# NanoEEG_v1_ADC.net
KiCad netlist of a schematic drawn in Altium Designer
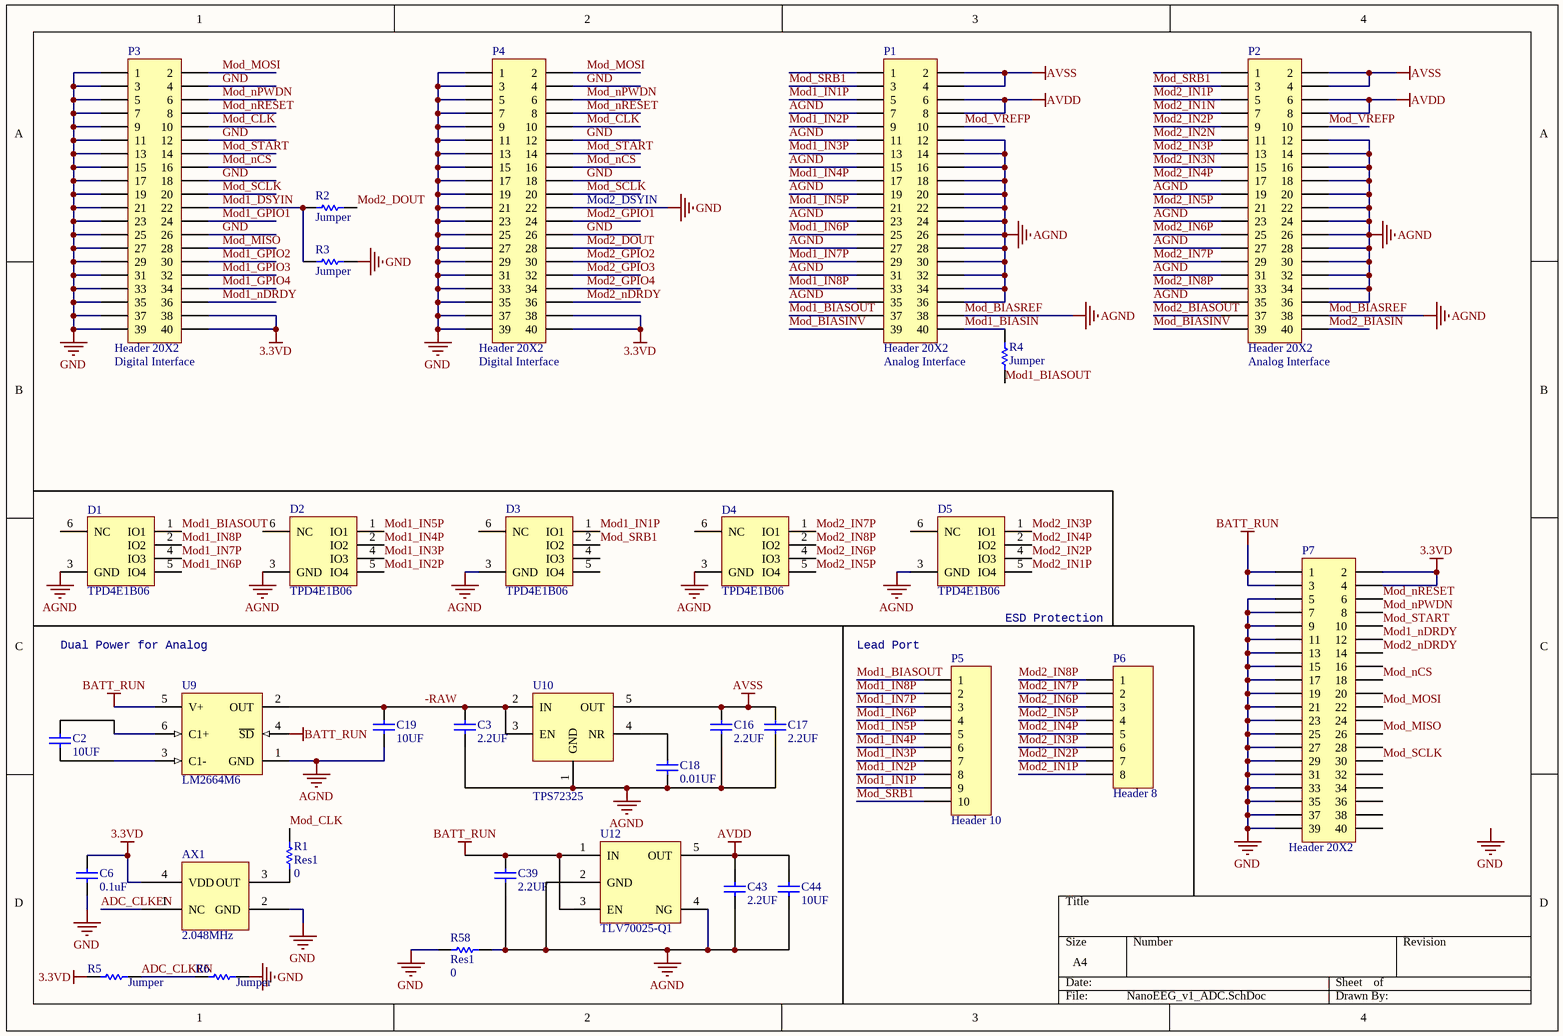
[diagram p0: NanoEEG_v1_ADC.SchDoc]

(export (version "E")
  (design (tool "Eeschema 10.0.6"))
  (components
    (comp (ref "AX1")
      (value "2.048MHz")
      (footprint "EPSON-SG-310-4_V")
      (libsource (lib "SMARTCAR09") (part "Active Cyrstal 5x7"))
    )
    (comp (ref "C2") (value "10UF") (footprint "RESC2012N") (libsource (lib "智能车") (part "CAP_0603")))
    (comp (ref "C3") (value "2.2UF") (footprint "RESC2012N") (libsource (lib "智能车") (part "CAP_0402")))
    (comp (ref "C6") (value "0.1uF") (footprint "RESC1608N") (libsource (lib "智能车") (part "电容")))
    (comp (ref "C16") (value "2.2UF") (footprint "RESC1608N") (libsource (lib "智能车") (part "RESC2012N")))
    (comp (ref "C17") (value "2.2UF") (footprint "RESC1608N") (libsource (lib "智能车") (part "RESC2012N")))
    (comp (ref "C18") (value "0.01UF") (footprint "RESC1608N") (libsource (lib "智能车") (part "RESC1608N")))
    (comp (ref "C19") (value "10UF") (footprint "RESC2012N") (libsource (lib "智能车") (part "CAP_0603")))
    (comp (ref "C39") (value "2.2UF") (footprint "RESC2012N") (libsource (lib "智能车") (part "CAP_0402")))
    (comp (ref "C43") (value "2.2UF") (footprint "RESC2012N") (libsource (lib "智能车") (part "CAP_0402")))
    (comp (ref "C44") (value "10UF") (footprint "RESC2012N") (libsource (lib "智能车") (part "CAP_0603")))
    (comp (ref "D1")
      (value "TPD4E1B06")
      (footprint "erjiguan")
      (libsource (lib "Trans_ETH") (part "TPD4E1B06"))
    )
    (comp (ref "D2")
      (value "TPD4E1B06")
      (footprint "erjiguan")
      (libsource (lib "Trans_ETH") (part "TPD4E1B06"))
    )
    (comp (ref "D3")
      (value "TPD4E1B06")
      (footprint "erjiguan")
      (libsource (lib "Trans_ETH") (part "TPD4E1B06"))
    )
    (comp (ref "D4")
      (value "TPD4E1B06")
      (footprint "erjiguan")
      (libsource (lib "Trans_ETH") (part "TPD4E1B06"))
    )
    (comp (ref "D5")
      (value "TPD4E1B06")
      (footprint "erjiguan")
      (libsource (lib "Trans_ETH") (part "TPD4E1B06"))
    )
    (comp (ref "P1")
      (value "Header 20X2")
      (footprint "FCI-B2B-0.8mm-40p-male")
      (description "Header, 20-Pin, Dual row")
      (fields (field (name "PUBLISHER") "Altium Limited"))
      (libsource (lib "Miscellaneous Connectors") (part "Header 20X2"))
    )
    (comp (ref "P2")
      (value "Header 20X2")
      (footprint "FCI-B2B-0.8mm-40p-MALE")
      (description "Header, 20-Pin, Dual row")
      (fields (field (name "PUBLISHER") "Altium Limited"))
      (libsource (lib "Miscellaneous Connectors") (part "Header 20X2"))
    )
    (comp (ref "P3")
      (value "Header 20X2")
      (footprint "FCI-B2B-0.8mm-40p-male")
      (description "Header, 20-Pin, Dual row")
      (fields (field (name "PUBLISHER") "Altium Limited"))
      (libsource (lib "Miscellaneous Connectors") (part "Header 20X2"))
    )
    (comp (ref "P4")
      (value "Header 20X2")
      (footprint "FCI-B2B-0.8mm-40p-MALE")
      (description "Header, 20-Pin, Dual row")
      (fields (field (name "PUBLISHER") "Altium Limited"))
      (libsource (lib "Miscellaneous Connectors") (part "Header 20X2"))
    )
    (comp (ref "P5")
      (value "Header 10")
      (footprint "PH2.0-WS-10P")
      (description "Header, 10-Pin")
      (fields (field (name "PUBLISHER") "Altium Limited"))
      (libsource (lib "Miscellaneous Connectors") (part "Header 10"))
    )
    (comp (ref "P6")
      (value "Header 8")
      (footprint "PH2.0-WS-8P")
      (description "Header, 8-Pin")
      (fields (field (name "PUBLISHER") "Altium Limited"))
      (libsource (lib "Miscellaneous Connectors") (part "Header 8"))
    )
    (comp (ref "P7")
      (value "Header 20X2")
      (footprint "FCI-B2B-0.8mm-40p-MALE")
      (description "Header, 20-Pin, Dual row")
      (fields (field (name "PUBLISHER") "Altium Limited"))
      (libsource (lib "Miscellaneous Connectors") (part "Header 20X2"))
    )
    (comp (ref "R1")
      (value "Res1")
      (footprint "RESC1608N")
      (description "Resistor")
      (fields (field (name "ALTIUM_VALUE") "0") (field (name "PUBLISHER") "Altium Limited"))
      (libsource (lib "Miscellaneous Devices") (part "Res1"))
    )
    (comp (ref "R2")
      (value "Jumper")
      (footprint "RESC0603(1608)_N")
      (description "Jumper 0603 (1608 Metric)")
      (fields (field (name "POWER") "None"))
      (libsource (lib "Altium Content Vault") (part "RES"))
    )
    (comp (ref "R3")
      (value "Jumper")
      (footprint "RESC0603(1608)_N")
      (description "Jumper 0603 (1608 Metric)")
      (fields (field (name "POWER") "None"))
      (libsource (lib "Altium Content Vault") (part "RES"))
    )
    (comp (ref "R4")
      (value "Jumper")
      (footprint "RESC0603(1608)_N")
      (description "Jumper 0603 (1608 Metric)")
      (fields (field (name "POWER") "None"))
      (libsource (lib "Altium Content Vault") (part "RES"))
    )
    (comp (ref "R5")
      (value "Jumper")
      (footprint "RESC0603(1608)_N")
      (description "Jumper 0603 (1608 Metric)")
      (fields (field (name "POWER") "None"))
      (libsource (lib "Altium Content Vault") (part "RES"))
    )
    (comp (ref "R6")
      (value "Jumper")
      (footprint "RESC0603(1608)_N")
      (description "Jumper 0603 (1608 Metric)")
      (fields (field (name "POWER") "None"))
      (libsource (lib "Altium Content Vault") (part "RES"))
    )
    (comp (ref "R58")
      (value "Res1")
      (footprint "RESC3225N")
      (description "Resistor")
      (fields (field (name "ALTIUM_VALUE") "0") (field (name "PUBLISHER") "Altium Limited"))
      (libsource (lib "Miscellaneous Devices") (part "Res1"))
    )
    (comp (ref "U9")
      (value "LM2664M6")
      (footprint "DBV0006A_N")
      (description "Switched Capacitor Voltage Converter, 6-pin SOT-23")
      (fields (field (name "MANUFACTURER") "Texas Instruments"))
      (libsource (lib "Altium Content Vault") (part "PM-CHP-LM2664M6-6"))
    )
    (comp (ref "U10")
      (value "TPS72325")
      (footprint "SOT23_5")
      (description "-2.5V")
      (libsource (lib "智能车") (part "TPS72325"))
    )
    (comp (ref "U12")
      (value "TLV70025-Q1")
      (footprint "SOT23_5")
      (libsource (lib "智能车") (part "TLV70025-Q1"))
    )
  )
  (nets
    (net (code "1") (name "/-RAW") (class "Default")
      (node (ref "C19") (pin "2") (pinfunction "2_2") (pintype "passive"))
      (node (ref "C3") (pin "2") (pinfunction "2_2") (pintype "passive"))
      (node (ref "U10") (pin "2") (pinfunction "IN_2") (pintype "passive"))
      (node (ref "U10") (pin "3") (pinfunction "EN_3") (pintype "passive"))
      (node (ref "U9") (pin "2") (pinfunction "OUT_2") (pintype "power_in"))
    )
    (net (code "2") (name "/ADC_CLKEN") (class "Default")
      (node (ref "AX1") (pin "1") (pinfunction "NC_1") (pintype "passive"))
      (node (ref "R5") (pin "2") (pinfunction "2_2") (pintype "passive"))
      (node (ref "R6") (pin "1") (pinfunction "1_1") (pintype "passive"))
    )
    (net (code "3") (name "/Mod1_BIASIN") (class "Default")
      (node (ref "P1") (pin "40") (pinfunction "40_40") (pintype "passive"))
      (node (ref "R4") (pin "1") (pinfunction "1_1") (pintype "passive"))
    )
    (net (code "4") (name "/Mod1_BIASOUT") (class "Default")
      (node (ref "D1") (pin "1") (pinfunction "IO1_1") (pintype "passive"))
      (node (ref "P1") (pin "37") (pinfunction "37_37") (pintype "passive"))
      (node (ref "P5") (pin "1") (pinfunction "1_1") (pintype "passive"))
      (node (ref "R4") (pin "2") (pinfunction "2_2") (pintype "passive"))
    )
    (net (code "5") (name "/Mod1_DSYIN") (class "Default")
      (node (ref "P3") (pin "22") (pinfunction "22_22") (pintype "passive"))
      (node (ref "R2") (pin "1") (pinfunction "1_1") (pintype "passive"))
      (node (ref "R3") (pin "1") (pinfunction "1_1") (pintype "passive"))
    )
    (net (code "6") (name "/Mod1_GPIO1") (class "Default")
      (node (ref "P3") (pin "24") (pinfunction "24_24") (pintype "passive"))
    )
    (net (code "7") (name "/Mod1_GPIO2") (class "Default")
      (node (ref "P3") (pin "30") (pinfunction "30_30") (pintype "passive"))
    )
    (net (code "8") (name "/Mod1_GPIO3") (class "Default")
      (node (ref "P3") (pin "32") (pinfunction "32_32") (pintype "passive"))
    )
    (net (code "9") (name "/Mod1_GPIO4") (class "Default")
      (node (ref "P3") (pin "34") (pinfunction "34_34") (pintype "passive"))
    )
    (net (code "10") (name "/Mod1_IN1P") (class "Default")
      (node (ref "D3") (pin "1") (pinfunction "IO1_1") (pintype "passive"))
      (node (ref "P1") (pin "5") (pinfunction "5_5") (pintype "passive"))
      (node (ref "P5") (pin "9") (pinfunction "9_9") (pintype "passive"))
    )
    (net (code "11") (name "/Mod1_IN2P") (class "Default")
      (node (ref "D2") (pin "5") (pinfunction "IO4_5") (pintype "passive"))
      (node (ref "P1") (pin "9") (pinfunction "9_9") (pintype "passive"))
      (node (ref "P5") (pin "8") (pinfunction "8_8") (pintype "passive"))
    )
    (net (code "12") (name "/Mod1_IN3P") (class "Default")
      (node (ref "D2") (pin "4") (pinfunction "IO3_4") (pintype "passive"))
      (node (ref "P1") (pin "13") (pinfunction "13_13") (pintype "passive"))
      (node (ref "P5") (pin "7") (pinfunction "7_7") (pintype "passive"))
    )
    (net (code "13") (name "/Mod1_IN4P") (class "Default")
      (node (ref "D2") (pin "2") (pinfunction "IO2_2") (pintype "passive"))
      (node (ref "P1") (pin "17") (pinfunction "17_17") (pintype "passive"))
      (node (ref "P5") (pin "6") (pinfunction "6_6") (pintype "passive"))
    )
    (net (code "14") (name "/Mod1_IN5P") (class "Default")
      (node (ref "D2") (pin "1") (pinfunction "IO1_1") (pintype "passive"))
      (node (ref "P1") (pin "21") (pinfunction "21_21") (pintype "passive"))
      (node (ref "P5") (pin "5") (pinfunction "5_5") (pintype "passive"))
    )
    (net (code "15") (name "/Mod1_IN6P") (class "Default")
      (node (ref "D1") (pin "5") (pinfunction "IO4_5") (pintype "passive"))
      (node (ref "P1") (pin "25") (pinfunction "25_25") (pintype "passive"))
      (node (ref "P5") (pin "4") (pinfunction "4_4") (pintype "passive"))
    )
    (net (code "16") (name "/Mod1_IN7P") (class "Default")
      (node (ref "D1") (pin "4") (pinfunction "IO3_4") (pintype "passive"))
      (node (ref "P1") (pin "29") (pinfunction "29_29") (pintype "passive"))
      (node (ref "P5") (pin "3") (pinfunction "3_3") (pintype "passive"))
    )
    (net (code "17") (name "/Mod1_IN8P") (class "Default")
      (node (ref "D1") (pin "2") (pinfunction "IO2_2") (pintype "passive"))
      (node (ref "P1") (pin "33") (pinfunction "33_33") (pintype "passive"))
      (node (ref "P5") (pin "2") (pinfunction "2_2") (pintype "passive"))
    )
    (net (code "18") (name "/Mod1_nDRDY") (class "Default")
      (node (ref "P3") (pin "36") (pinfunction "36_36") (pintype "passive"))
      (node (ref "P7") (pin "12") (pinfunction "12_12") (pintype "passive"))
    )
    (net (code "19") (name "/Mod2_BIASIN") (class "Default")
      (node (ref "P2") (pin "40") (pinfunction "40_40") (pintype "passive"))
    )
    (net (code "20") (name "/Mod2_BIASOUT") (class "Default")
      (node (ref "P2") (pin "37") (pinfunction "37_37") (pintype "passive"))
    )
    (net (code "21") (name "/Mod2_DOUT") (class "Default")
      (node (ref "P4") (pin "28") (pinfunction "28_28") (pintype "passive"))
      (node (ref "R2") (pin "2") (pinfunction "2_2") (pintype "passive"))
    )
    (net (code "22") (name "/Mod2_GPIO1") (class "Default")
      (node (ref "P4") (pin "24") (pinfunction "24_24") (pintype "passive"))
    )
    (net (code "23") (name "/Mod2_GPIO2") (class "Default")
      (node (ref "P4") (pin "30") (pinfunction "30_30") (pintype "passive"))
    )
    (net (code "24") (name "/Mod2_GPIO3") (class "Default")
      (node (ref "P4") (pin "32") (pinfunction "32_32") (pintype "passive"))
    )
    (net (code "25") (name "/Mod2_GPIO4") (class "Default")
      (node (ref "P4") (pin "34") (pinfunction "34_34") (pintype "passive"))
    )
    (net (code "26") (name "/Mod2_IN1N") (class "Default")
      (node (ref "P2") (pin "7") (pinfunction "7_7") (pintype "passive"))
    )
    (net (code "27") (name "/Mod2_IN1P") (class "Default")
      (node (ref "D5") (pin "5") (pinfunction "IO4_5") (pintype "passive"))
      (node (ref "P2") (pin "5") (pinfunction "5_5") (pintype "passive"))
      (node (ref "P6") (pin "8") (pinfunction "8_8") (pintype "passive"))
    )
    (net (code "28") (name "/Mod2_IN2N") (class "Default")
      (node (ref "P2") (pin "11") (pinfunction "11_11") (pintype "passive"))
    )
    (net (code "29") (name "/Mod2_IN2P") (class "Default")
      (node (ref "D5") (pin "4") (pinfunction "IO3_4") (pintype "passive"))
      (node (ref "P2") (pin "9") (pinfunction "9_9") (pintype "passive"))
      (node (ref "P6") (pin "7") (pinfunction "7_7") (pintype "passive"))
    )
    (net (code "30") (name "/Mod2_IN3N") (class "Default")
      (node (ref "P2") (pin "15") (pinfunction "15_15") (pintype "passive"))
    )
    (net (code "31") (name "/Mod2_IN3P") (class "Default")
      (node (ref "D5") (pin "1") (pinfunction "IO1_1") (pintype "passive"))
      (node (ref "P2") (pin "13") (pinfunction "13_13") (pintype "passive"))
      (node (ref "P6") (pin "6") (pinfunction "6_6") (pintype "passive"))
    )
    (net (code "32") (name "/Mod2_IN4P") (class "Default")
      (node (ref "D5") (pin "2") (pinfunction "IO2_2") (pintype "passive"))
      (node (ref "P2") (pin "17") (pinfunction "17_17") (pintype "passive"))
      (node (ref "P6") (pin "5") (pinfunction "5_5") (pintype "passive"))
    )
    (net (code "33") (name "/Mod2_IN5P") (class "Default")
      (node (ref "D4") (pin "5") (pinfunction "IO4_5") (pintype "passive"))
      (node (ref "P2") (pin "21") (pinfunction "21_21") (pintype "passive"))
      (node (ref "P6") (pin "4") (pinfunction "4_4") (pintype "passive"))
    )
    (net (code "34") (name "/Mod2_IN6P") (class "Default")
      (node (ref "D4") (pin "4") (pinfunction "IO3_4") (pintype "passive"))
      (node (ref "P2") (pin "25") (pinfunction "25_25") (pintype "passive"))
      (node (ref "P6") (pin "3") (pinfunction "3_3") (pintype "passive"))
    )
    (net (code "35") (name "/Mod2_IN7P") (class "Default")
      (node (ref "D4") (pin "1") (pinfunction "IO1_1") (pintype "passive"))
      (node (ref "P2") (pin "29") (pinfunction "29_29") (pintype "passive"))
      (node (ref "P6") (pin "2") (pinfunction "2_2") (pintype "passive"))
    )
    (net (code "36") (name "/Mod2_IN8P") (class "Default")
      (node (ref "D4") (pin "2") (pinfunction "IO2_2") (pintype "passive"))
      (node (ref "P2") (pin "33") (pinfunction "33_33") (pintype "passive"))
      (node (ref "P6") (pin "1") (pinfunction "1_1") (pintype "passive"))
    )
    (net (code "37") (name "/Mod2_nDRDY") (class "Default")
      (node (ref "P4") (pin "36") (pinfunction "36_36") (pintype "passive"))
      (node (ref "P7") (pin "14") (pinfunction "14_14") (pintype "passive"))
    )
    (net (code "38") (name "/Mod_BIASINV") (class "Default")
      (node (ref "P1") (pin "39") (pinfunction "39_39") (pintype "passive"))
      (node (ref "P2") (pin "39") (pinfunction "39_39") (pintype "passive"))
    )
    (net (code "39") (name "/Mod_CLK") (class "Default")
      (node (ref "P3") (pin "10") (pinfunction "10_10") (pintype "passive"))
      (node (ref "P4") (pin "10") (pinfunction "10_10") (pintype "passive"))
      (node (ref "R1") (pin "2") (pinfunction "2_2") (pintype "passive"))
    )
    (net (code "40") (name "/Mod_MISO") (class "Default")
      (node (ref "P3") (pin "28") (pinfunction "28_28") (pintype "passive"))
      (node (ref "P7") (pin "26") (pinfunction "26_26") (pintype "passive"))
    )
    (net (code "41") (name "/Mod_MOSI") (class "Default")
      (node (ref "P3") (pin "2") (pinfunction "2_2") (pintype "passive"))
      (node (ref "P4") (pin "2") (pinfunction "2_2") (pintype "passive"))
      (node (ref "P7") (pin "22") (pinfunction "22_22") (pintype "passive"))
    )
    (net (code "42") (name "/Mod_SCLK") (class "Default")
      (node (ref "P3") (pin "20") (pinfunction "20_20") (pintype "passive"))
      (node (ref "P4") (pin "20") (pinfunction "20_20") (pintype "passive"))
      (node (ref "P7") (pin "30") (pinfunction "30_30") (pintype "passive"))
    )
    (net (code "43") (name "/Mod_SRB1") (class "Default")
      (node (ref "D3") (pin "2") (pinfunction "IO2_2") (pintype "passive"))
      (node (ref "P1") (pin "3") (pinfunction "3_3") (pintype "passive"))
      (node (ref "P2") (pin "3") (pinfunction "3_3") (pintype "passive"))
      (node (ref "P5") (pin "10") (pinfunction "10_10") (pintype "passive"))
    )
    (net (code "44") (name "/Mod_START") (class "Default")
      (node (ref "P3") (pin "14") (pinfunction "14_14") (pintype "passive"))
      (node (ref "P4") (pin "14") (pinfunction "14_14") (pintype "passive"))
      (node (ref "P7") (pin "10") (pinfunction "10_10") (pintype "passive"))
    )
    (net (code "45") (name "/Mod_VREFP") (class "Default")
      (node (ref "P1") (pin "10") (pinfunction "10_10") (pintype "passive"))
      (node (ref "P2") (pin "10") (pinfunction "10_10") (pintype "passive"))
    )
    (net (code "46") (name "/Mod_nCS") (class "Default")
      (node (ref "P3") (pin "16") (pinfunction "16_16") (pintype "passive"))
      (node (ref "P4") (pin "16") (pinfunction "16_16") (pintype "passive"))
      (node (ref "P7") (pin "18") (pinfunction "18_18") (pintype "passive"))
    )
    (net (code "47") (name "/Mod_nPWDN") (class "Default")
      (node (ref "P3") (pin "6") (pinfunction "6_6") (pintype "passive"))
      (node (ref "P4") (pin "6") (pinfunction "6_6") (pintype "passive"))
      (node (ref "P7") (pin "8") (pinfunction "8_8") (pintype "passive"))
    )
    (net (code "48") (name "/Mod_nRESET") (class "Default")
      (node (ref "P3") (pin "8") (pinfunction "8_8") (pintype "passive"))
      (node (ref "P4") (pin "8") (pinfunction "8_8") (pintype "passive"))
      (node (ref "P7") (pin "6") (pinfunction "6_6") (pintype "passive"))
    )
    (net (code "49") (name "3.3VD") (class "Default")
      (node (ref "AX1") (pin "4") (pinfunction "VDD_4") (pintype "passive"))
      (node (ref "C6") (pin "1") (pinfunction "1_1") (pintype "passive"))
      (node (ref "P3") (pin "38") (pinfunction "38_38") (pintype "passive"))
      (node (ref "P3") (pin "40") (pinfunction "40_40") (pintype "passive"))
      (node (ref "P4") (pin "38") (pinfunction "38_38") (pintype "passive"))
      (node (ref "P4") (pin "40") (pinfunction "40_40") (pintype "passive"))
      (node (ref "P7") (pin "2") (pinfunction "2_2") (pintype "passive"))
      (node (ref "P7") (pin "4") (pinfunction "4_4") (pintype "passive"))
      (node (ref "R5") (pin "1") (pinfunction "1_1") (pintype "passive"))
    )
    (net (code "50") (name "AGND") (class "Default")
      (node (ref "C16") (pin "1") (pinfunction "1_1") (pintype "passive"))
      (node (ref "C17") (pin "1") (pinfunction "1_1") (pintype "passive"))
      (node (ref "C18") (pin "1") (pinfunction "1_1") (pintype "passive"))
      (node (ref "C19") (pin "1") (pinfunction "1_1") (pintype "passive"))
      (node (ref "C3") (pin "1") (pinfunction "1_1") (pintype "passive"))
      (node (ref "C39") (pin "1") (pinfunction "1_1") (pintype "passive"))
      (node (ref "C43") (pin "1") (pinfunction "1_1") (pintype "passive"))
      (node (ref "C44") (pin "1") (pinfunction "1_1") (pintype "passive"))
      (node (ref "D1") (pin "3") (pinfunction "GND_3") (pintype "passive"))
      (node (ref "D2") (pin "3") (pinfunction "GND_3") (pintype "passive"))
      (node (ref "D3") (pin "3") (pinfunction "GND_3") (pintype "passive"))
      (node (ref "D4") (pin "3") (pinfunction "GND_3") (pintype "passive"))
      (node (ref "D5") (pin "3") (pinfunction "GND_3") (pintype "passive"))
      (node (ref "P1") (pin "11") (pinfunction "11_11") (pintype "passive"))
      (node (ref "P1") (pin "12") (pinfunction "12_12") (pintype "passive"))
      (node (ref "P1") (pin "14") (pinfunction "14_14") (pintype "passive"))
      (node (ref "P1") (pin "15") (pinfunction "15_15") (pintype "passive"))
      (node (ref "P1") (pin "16") (pinfunction "16_16") (pintype "passive"))
      (node (ref "P1") (pin "18") (pinfunction "18_18") (pintype "passive"))
      (node (ref "P1") (pin "19") (pinfunction "19_19") (pintype "passive"))
      (node (ref "P1") (pin "20") (pinfunction "20_20") (pintype "passive"))
      (node (ref "P1") (pin "22") (pinfunction "22_22") (pintype "passive"))
      (node (ref "P1") (pin "23") (pinfunction "23_23") (pintype "passive"))
      (node (ref "P1") (pin "24") (pinfunction "24_24") (pintype "passive"))
      (node (ref "P1") (pin "26") (pinfunction "26_26") (pintype "passive"))
      (node (ref "P1") (pin "27") (pinfunction "27_27") (pintype "passive"))
      (node (ref "P1") (pin "28") (pinfunction "28_28") (pintype "passive"))
      (node (ref "P1") (pin "30") (pinfunction "30_30") (pintype "passive"))
      (node (ref "P1") (pin "31") (pinfunction "31_31") (pintype "passive"))
      (node (ref "P1") (pin "32") (pinfunction "32_32") (pintype "passive"))
      (node (ref "P1") (pin "34") (pinfunction "34_34") (pintype "passive"))
      (node (ref "P1") (pin "35") (pinfunction "35_35") (pintype "passive"))
      (node (ref "P1") (pin "36") (pinfunction "36_36") (pintype "passive"))
      (node (ref "P1") (pin "38") (pinfunction "38_38") (pintype "passive"))
      (node (ref "P1") (pin "7") (pinfunction "7_7") (pintype "passive"))
      (node (ref "P2") (pin "12") (pinfunction "12_12") (pintype "passive"))
      (node (ref "P2") (pin "14") (pinfunction "14_14") (pintype "passive"))
      (node (ref "P2") (pin "16") (pinfunction "16_16") (pintype "passive"))
      (node (ref "P2") (pin "18") (pinfunction "18_18") (pintype "passive"))
      (node (ref "P2") (pin "19") (pinfunction "19_19") (pintype "passive"))
      (node (ref "P2") (pin "20") (pinfunction "20_20") (pintype "passive"))
      (node (ref "P2") (pin "22") (pinfunction "22_22") (pintype "passive"))
      (node (ref "P2") (pin "23") (pinfunction "23_23") (pintype "passive"))
      (node (ref "P2") (pin "24") (pinfunction "24_24") (pintype "passive"))
      (node (ref "P2") (pin "26") (pinfunction "26_26") (pintype "passive"))
      (node (ref "P2") (pin "27") (pinfunction "27_27") (pintype "passive"))
      (node (ref "P2") (pin "28") (pinfunction "28_28") (pintype "passive"))
      (node (ref "P2") (pin "30") (pinfunction "30_30") (pintype "passive"))
      (node (ref "P2") (pin "31") (pinfunction "31_31") (pintype "passive"))
      (node (ref "P2") (pin "32") (pinfunction "32_32") (pintype "passive"))
      (node (ref "P2") (pin "34") (pinfunction "34_34") (pintype "passive"))
      (node (ref "P2") (pin "35") (pinfunction "35_35") (pintype "passive"))
      (node (ref "P2") (pin "36") (pinfunction "36_36") (pintype "passive"))
      (node (ref "P2") (pin "38") (pinfunction "38_38") (pintype "passive"))
      (node (ref "R58") (pin "1") (pinfunction "1_1") (pintype "passive"))
      (node (ref "U10") (pin "1") (pinfunction "GND_1") (pintype "passive"))
      (node (ref "U12") (pin "2") (pinfunction "GND_2") (pintype "passive"))
      (node (ref "U12") (pin "4") (pinfunction "NG_4") (pintype "passive"))
      (node (ref "U9") (pin "1") (pinfunction "GND_1") (pintype "power_in"))
    )
    (net (code "51") (name "AVDD") (class "Default")
      (node (ref "C43") (pin "2") (pinfunction "2_2") (pintype "passive"))
      (node (ref "C44") (pin "2") (pinfunction "2_2") (pintype "passive"))
      (node (ref "P1") (pin "6") (pinfunction "6_6") (pintype "passive"))
      (node (ref "P1") (pin "8") (pinfunction "8_8") (pintype "passive"))
      (node (ref "P2") (pin "6") (pinfunction "6_6") (pintype "passive"))
      (node (ref "P2") (pin "8") (pinfunction "8_8") (pintype "passive"))
      (node (ref "U12") (pin "5") (pinfunction "OUT_5") (pintype "passive"))
    )
    (net (code "52") (name "AVSS") (class "Default")
      (node (ref "C16") (pin "2") (pinfunction "2_2") (pintype "passive"))
      (node (ref "C17") (pin "2") (pinfunction "2_2") (pintype "passive"))
      (node (ref "P1") (pin "2") (pinfunction "2_2") (pintype "passive"))
      (node (ref "P1") (pin "4") (pinfunction "4_4") (pintype "passive"))
      (node (ref "P2") (pin "2") (pinfunction "2_2") (pintype "passive"))
      (node (ref "P2") (pin "4") (pinfunction "4_4") (pintype "passive"))
      (node (ref "U10") (pin "5") (pinfunction "OUT_5") (pintype "passive"))
    )
    (net (code "53") (name "BATT_RUN") (class "Default")
      (node (ref "C39") (pin "2") (pinfunction "2_2") (pintype "passive"))
      (node (ref "P7") (pin "1") (pinfunction "1_1") (pintype "passive"))
      (node (ref "P7") (pin "3") (pinfunction "3_3") (pintype "passive"))
      (node (ref "U12") (pin "1") (pinfunction "IN_1") (pintype "passive"))
      (node (ref "U12") (pin "3") (pinfunction "EN_3") (pintype "passive"))
      (node (ref "U9") (pin "4") (pinfunction "~{SD}_4") (pintype "input"))
      (node (ref "U9") (pin "5") (pinfunction "V+_5") (pintype "power_in"))
    )
    (net (code "54") (name "GND") (class "Default")
      (node (ref "AX1") (pin "2") (pinfunction "GND_2") (pintype "passive"))
      (node (ref "C6") (pin "2") (pinfunction "2_2") (pintype "passive"))
      (node (ref "P3") (pin "1") (pinfunction "1_1") (pintype "passive"))
      (node (ref "P3") (pin "11") (pinfunction "11_11") (pintype "passive"))
      (node (ref "P3") (pin "12") (pinfunction "12_12") (pintype "passive"))
      (node (ref "P3") (pin "13") (pinfunction "13_13") (pintype "passive"))
      (node (ref "P3") (pin "15") (pinfunction "15_15") (pintype "passive"))
      (node (ref "P3") (pin "17") (pinfunction "17_17") (pintype "passive"))
      (node (ref "P3") (pin "18") (pinfunction "18_18") (pintype "passive"))
      (node (ref "P3") (pin "19") (pinfunction "19_19") (pintype "passive"))
      (node (ref "P3") (pin "21") (pinfunction "21_21") (pintype "passive"))
      (node (ref "P3") (pin "23") (pinfunction "23_23") (pintype "passive"))
      (node (ref "P3") (pin "25") (pinfunction "25_25") (pintype "passive"))
      (node (ref "P3") (pin "26") (pinfunction "26_26") (pintype "passive"))
      (node (ref "P3") (pin "27") (pinfunction "27_27") (pintype "passive"))
      (node (ref "P3") (pin "29") (pinfunction "29_29") (pintype "passive"))
      (node (ref "P3") (pin "3") (pinfunction "3_3") (pintype "passive"))
      (node (ref "P3") (pin "31") (pinfunction "31_31") (pintype "passive"))
      (node (ref "P3") (pin "33") (pinfunction "33_33") (pintype "passive"))
      (node (ref "P3") (pin "35") (pinfunction "35_35") (pintype "passive"))
      (node (ref "P3") (pin "37") (pinfunction "37_37") (pintype "passive"))
      (node (ref "P3") (pin "39") (pinfunction "39_39") (pintype "passive"))
      (node (ref "P3") (pin "4") (pinfunction "4_4") (pintype "passive"))
      (node (ref "P3") (pin "5") (pinfunction "5_5") (pintype "passive"))
      (node (ref "P3") (pin "7") (pinfunction "7_7") (pintype "passive"))
      (node (ref "P3") (pin "9") (pinfunction "9_9") (pintype "passive"))
      (node (ref "P4") (pin "1") (pinfunction "1_1") (pintype "passive"))
      (node (ref "P4") (pin "11") (pinfunction "11_11") (pintype "passive"))
      (node (ref "P4") (pin "12") (pinfunction "12_12") (pintype "passive"))
      (node (ref "P4") (pin "13") (pinfunction "13_13") (pintype "passive"))
      (node (ref "P4") (pin "15") (pinfunction "15_15") (pintype "passive"))
      (node (ref "P4") (pin "17") (pinfunction "17_17") (pintype "passive"))
      (node (ref "P4") (pin "18") (pinfunction "18_18") (pintype "passive"))
      (node (ref "P4") (pin "19") (pinfunction "19_19") (pintype "passive"))
      (node (ref "P4") (pin "21") (pinfunction "21_21") (pintype "passive"))
      (node (ref "P4") (pin "22") (pinfunction "22_22") (pintype "passive"))
      (node (ref "P4") (pin "23") (pinfunction "23_23") (pintype "passive"))
      (node (ref "P4") (pin "25") (pinfunction "25_25") (pintype "passive"))
      (node (ref "P4") (pin "26") (pinfunction "26_26") (pintype "passive"))
      (node (ref "P4") (pin "27") (pinfunction "27_27") (pintype "passive"))
      (node (ref "P4") (pin "29") (pinfunction "29_29") (pintype "passive"))
      (node (ref "P4") (pin "3") (pinfunction "3_3") (pintype "passive"))
      (node (ref "P4") (pin "31") (pinfunction "31_31") (pintype "passive"))
      (node (ref "P4") (pin "33") (pinfunction "33_33") (pintype "passive"))
      (node (ref "P4") (pin "35") (pinfunction "35_35") (pintype "passive"))
      (node (ref "P4") (pin "37") (pinfunction "37_37") (pintype "passive"))
      (node (ref "P4") (pin "39") (pinfunction "39_39") (pintype "passive"))
      (node (ref "P4") (pin "4") (pinfunction "4_4") (pintype "passive"))
      (node (ref "P4") (pin "5") (pinfunction "5_5") (pintype "passive"))
      (node (ref "P4") (pin "7") (pinfunction "7_7") (pintype "passive"))
      (node (ref "P4") (pin "9") (pinfunction "9_9") (pintype "passive"))
      (node (ref "P7") (pin "11") (pinfunction "11_11") (pintype "passive"))
      (node (ref "P7") (pin "13") (pinfunction "13_13") (pintype "passive"))
      (node (ref "P7") (pin "15") (pinfunction "15_15") (pintype "passive"))
      (node (ref "P7") (pin "17") (pinfunction "17_17") (pintype "passive"))
      (node (ref "P7") (pin "19") (pinfunction "19_19") (pintype "passive"))
      (node (ref "P7") (pin "21") (pinfunction "21_21") (pintype "passive"))
      (node (ref "P7") (pin "23") (pinfunction "23_23") (pintype "passive"))
      (node (ref "P7") (pin "25") (pinfunction "25_25") (pintype "passive"))
      (node (ref "P7") (pin "27") (pinfunction "27_27") (pintype "passive"))
      (node (ref "P7") (pin "29") (pinfunction "29_29") (pintype "passive"))
      (node (ref "P7") (pin "31") (pinfunction "31_31") (pintype "passive"))
      (node (ref "P7") (pin "33") (pinfunction "33_33") (pintype "passive"))
      (node (ref "P7") (pin "35") (pinfunction "35_35") (pintype "passive"))
      (node (ref "P7") (pin "37") (pinfunction "37_37") (pintype "passive"))
      (node (ref "P7") (pin "39") (pinfunction "39_39") (pintype "passive"))
      (node (ref "P7") (pin "5") (pinfunction "5_5") (pintype "passive"))
      (node (ref "P7") (pin "7") (pinfunction "7_7") (pintype "passive"))
      (node (ref "P7") (pin "9") (pinfunction "9_9") (pintype "passive"))
      (node (ref "R3") (pin "2") (pinfunction "2_2") (pintype "passive"))
      (node (ref "R58") (pin "2") (pinfunction "2_2") (pintype "passive"))
      (node (ref "R6") (pin "2") (pinfunction "2_2") (pintype "passive"))
    )
    (net (code "55") (name "Net-(AX1-OUT)") (class "Default")
      (node (ref "AX1") (pin "3") (pinfunction "OUT_3") (pintype "passive"))
      (node (ref "R1") (pin "1") (pinfunction "1_1") (pintype "passive"))
    )
    (net (code "56") (name "Net-(U9-C1+)") (class "Default")
      (node (ref "C2") (pin "2") (pinfunction "2_2") (pintype "passive"))
      (node (ref "U9") (pin "6") (pinfunction "C1+_6") (pintype "input"))
    )
    (net (code "57") (name "Net-(U9-C1-)") (class "Default")
      (node (ref "C2") (pin "1") (pinfunction "1_1") (pintype "passive"))
      (node (ref "U9") (pin "3") (pinfunction "C1-_3") (pintype "input"))
    )
    (net (code "58") (name "Net-(U10-NR)") (class "Default")
      (node (ref "C18") (pin "2") (pinfunction "2_2") (pintype "passive"))
      (node (ref "U10") (pin "4") (pinfunction "NR_4") (pintype "passive"))
    )
    (net (code "59") (name "unconnected-(D1-NC-Pad6)") (class "Default")
      (node (ref "D1") (pin "6") (pinfunction "NC_6") (pintype "passive"))
    )
    (net (code "60") (name "unconnected-(D2-NC-Pad6)") (class "Default")
      (node (ref "D2") (pin "6") (pinfunction "NC_6") (pintype "passive"))
    )
    (net (code "61") (name "unconnected-(D3-IO3-Pad4)") (class "Default")
      (node (ref "D3") (pin "4") (pinfunction "IO3_4") (pintype "passive"))
    )
    (net (code "62") (name "unconnected-(D3-IO4-Pad5)") (class "Default")
      (node (ref "D3") (pin "5") (pinfunction "IO4_5") (pintype "passive"))
    )
    (net (code "63") (name "unconnected-(D3-NC-Pad6)") (class "Default")
      (node (ref "D3") (pin "6") (pinfunction "NC_6") (pintype "passive"))
    )
    (net (code "64") (name "unconnected-(D4-NC-Pad6)") (class "Default")
      (node (ref "D4") (pin "6") (pinfunction "NC_6") (pintype "passive"))
    )
    (net (code "65") (name "unconnected-(D5-NC-Pad6)") (class "Default")
      (node (ref "D5") (pin "6") (pinfunction "NC_6") (pintype "passive"))
    )
    (net (code "66") (name "unconnected-(P1-Pad1)") (class "Default")
      (node (ref "P1") (pin "1") (pinfunction "1_1") (pintype "passive"))
    )
    (net (code "67") (name "unconnected-(P2-Pad1)") (class "Default")
      (node (ref "P2") (pin "1") (pinfunction "1_1") (pintype "passive"))
    )
    (net (code "68") (name "unconnected-(P7-Pad16)") (class "Default")
      (node (ref "P7") (pin "16") (pinfunction "16_16") (pintype "passive"))
    )
    (net (code "69") (name "unconnected-(P7-Pad20)") (class "Default")
      (node (ref "P7") (pin "20") (pinfunction "20_20") (pintype "passive"))
    )
    (net (code "70") (name "unconnected-(P7-Pad24)") (class "Default")
      (node (ref "P7") (pin "24") (pinfunction "24_24") (pintype "passive"))
    )
    (net (code "71") (name "unconnected-(P7-Pad28)") (class "Default")
      (node (ref "P7") (pin "28") (pinfunction "28_28") (pintype "passive"))
    )
    (net (code "72") (name "unconnected-(P7-Pad32)") (class "Default")
      (node (ref "P7") (pin "32") (pinfunction "32_32") (pintype "passive"))
    )
    (net (code "73") (name "unconnected-(P7-Pad34)") (class "Default")
      (node (ref "P7") (pin "34") (pinfunction "34_34") (pintype "passive"))
    )
    (net (code "74") (name "unconnected-(P7-Pad36)") (class "Default")
      (node (ref "P7") (pin "36") (pinfunction "36_36") (pintype "passive"))
    )
    (net (code "75") (name "unconnected-(P7-Pad38)") (class "Default")
      (node (ref "P7") (pin "38") (pinfunction "38_38") (pintype "passive"))
    )
    (net (code "76") (name "unconnected-(P7-Pad40)") (class "Default")
      (node (ref "P7") (pin "40") (pinfunction "40_40") (pintype "passive"))
    )
  )
)
